# Bluetooth_LMC9830SM.net
KiCad netlist of a schematic drawn in Altium Designer
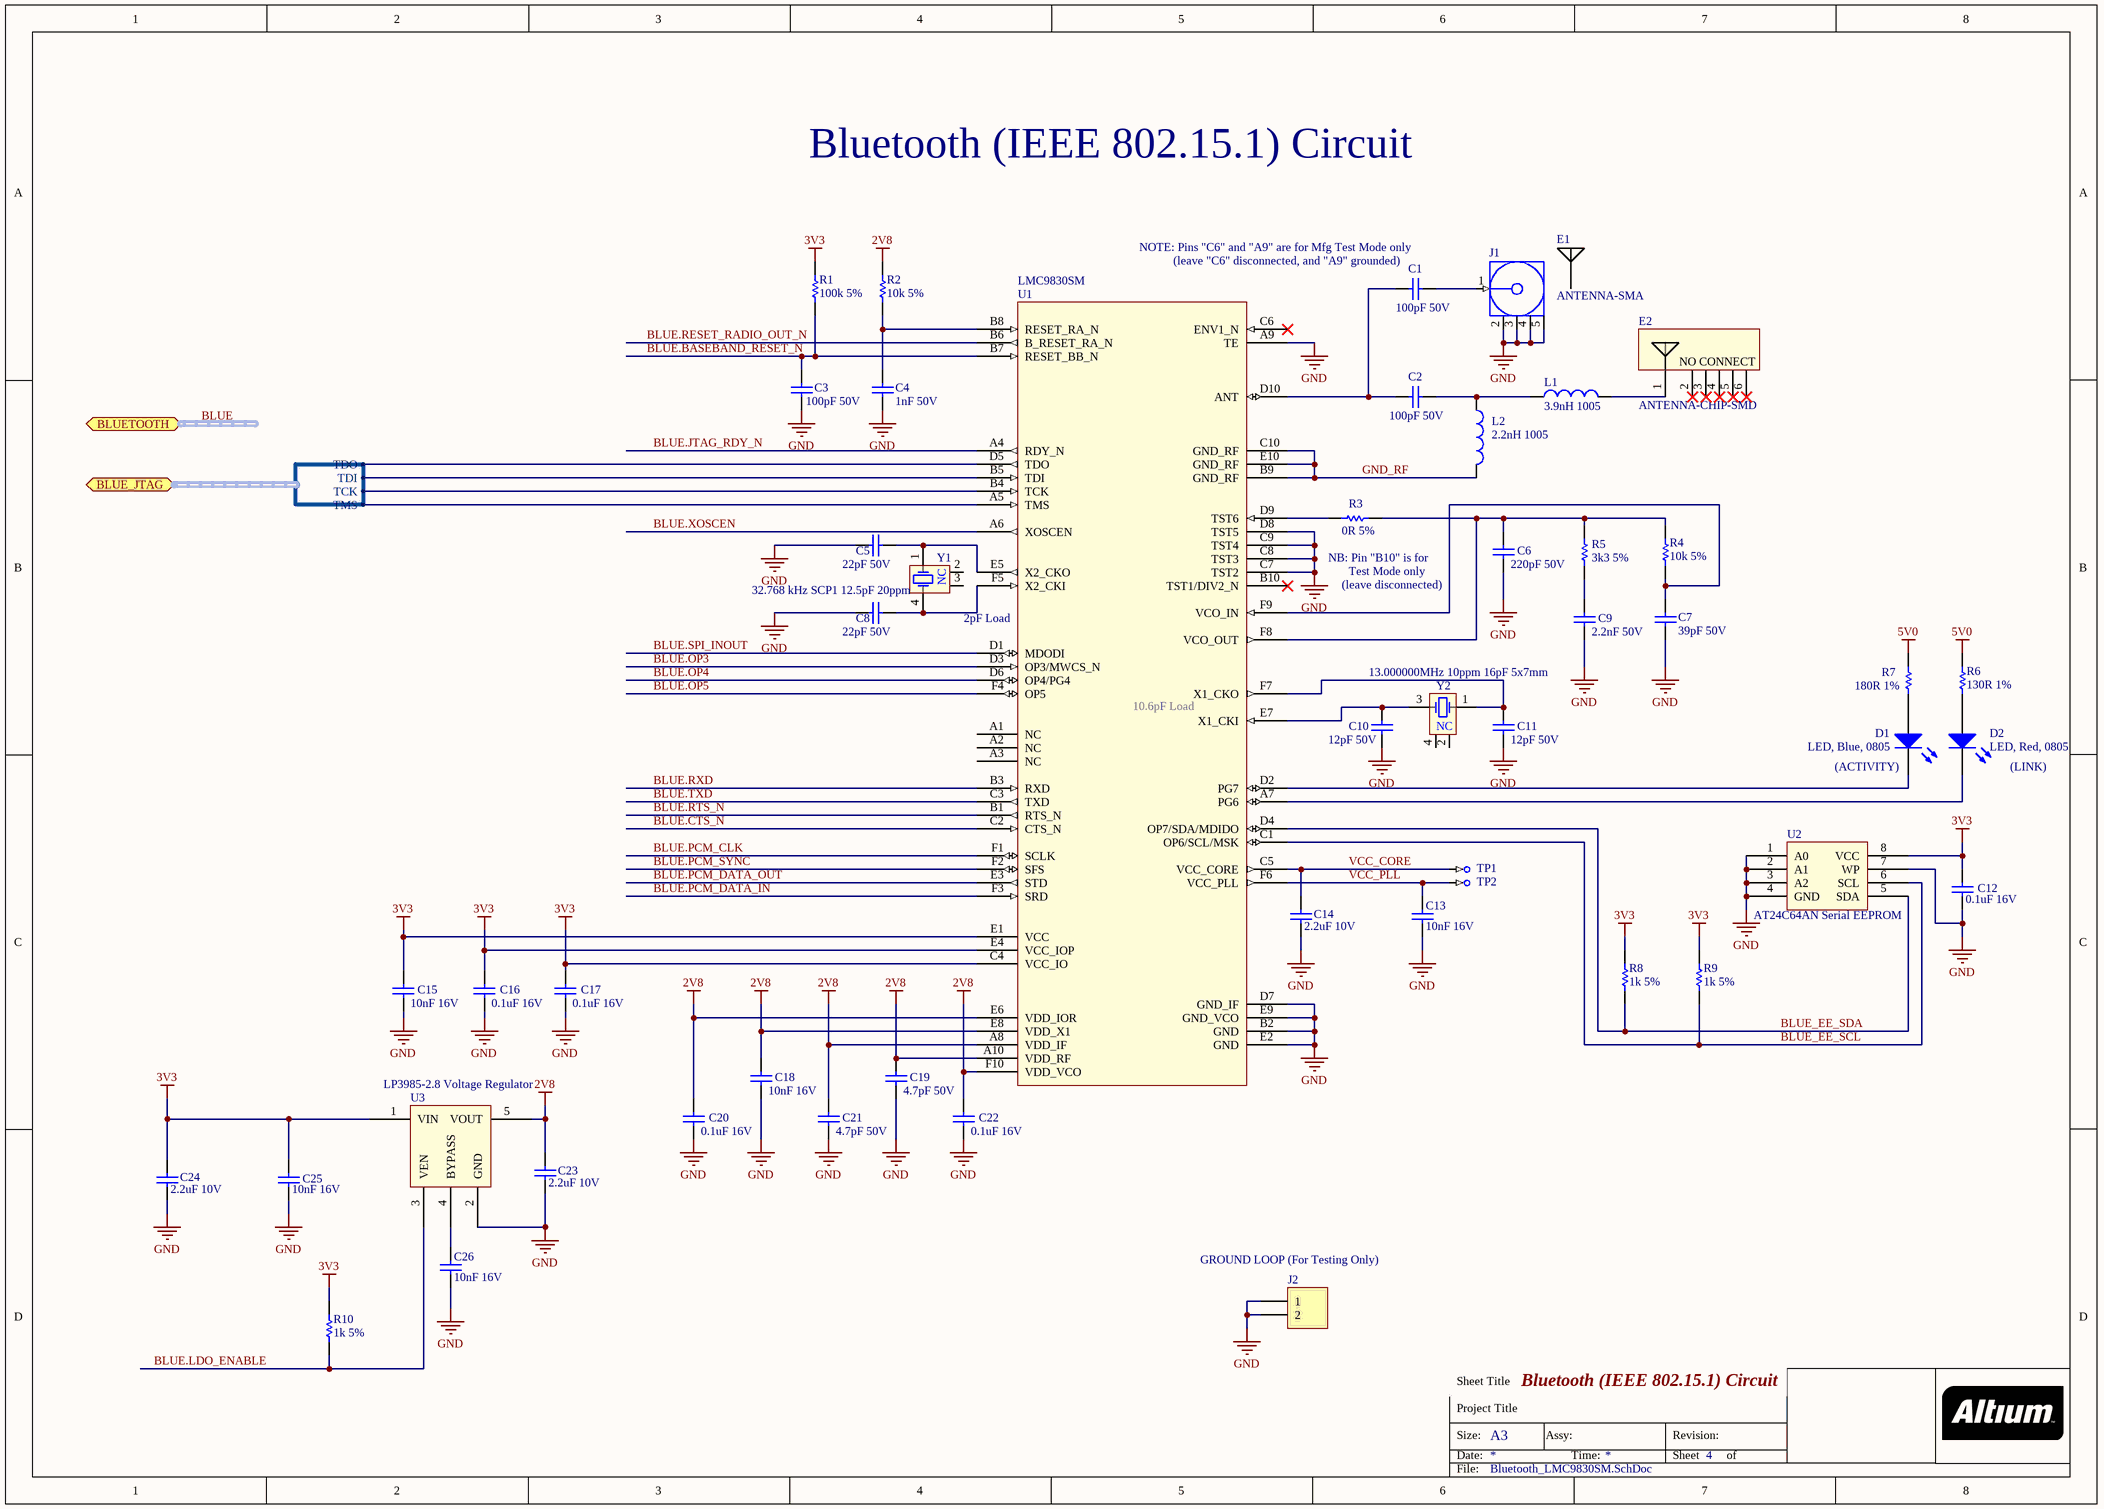
[diagram p0: Bluetooth_LMC9830SM.SchDoc]

(export (version "E")
  (design (tool "Eeschema 10.0.6"))
  (components
    (comp (ref "C1")
      (value "100pF 50V")
      (footprint "CAPC1005-STAR")
      (description "Capacitor, Ceramic, 100pF 5% 50V 0402 (1005) COG")
      (fields (field (name "TOLERANCE") "5 %"))
      (libsource (lib "AltiumDesignLibrary") (part "CAP-NP"))
    )
    (comp (ref "C2")
      (value "100pF 50V")
      (footprint "CAPC1005-STAR")
      (description "Capacitor, Ceramic, 100pF 5% 50V 0402 (1005) COG")
      (fields (field (name "TOLERANCE") "5 %"))
      (libsource (lib "AltiumDesignLibrary") (part "CAP-NP"))
    )
    (comp (ref "C3")
      (value "100pF 50V")
      (footprint "CAPC1005-STAR")
      (description "Capacitor, Ceramic, 100pF 5% 50V 0402 (1005) COG")
      (fields (field (name "TOLERANCE") "5 %"))
      (libsource (lib "AltiumDesignLibrary") (part "CAP-NP"))
    )
    (comp (ref "C4")
      (value "1nF 50V")
      (footprint "CAPC1005-STAR")
      (description "Capacitor, Ceramic, 1nF 10% 50V 0402 (1005) X7R")
      (fields (field (name "TOLERANCE") "10 %"))
      (libsource (lib "AltiumDesignLibrary") (part "CAP-NP"))
    )
    (comp (ref "C5")
      (value "22pF 50V")
      (footprint "CAPC1005-STAR")
      (description "Capacitor, Ceramic, 22pF 5% 50V 0402 (1005) COG")
      (fields (field (name "TOLERANCE") "5 %"))
      (libsource (lib "AltiumDesignLibrary") (part "CAP-NP"))
    )
    (comp (ref "C6")
      (value "220pF 50V")
      (footprint "CAPC1005-STAR")
      (description "Capacitor, Ceramic, 220pF 5% 50V 0402 (1005) COG")
      (fields (field (name "TOLERANCE") "5 %"))
      (libsource (lib "AltiumDesignLibrary") (part "CAP-NP"))
    )
    (comp (ref "C7")
      (value "39pF 50V")
      (footprint "CAPC1005-STAR")
      (description "Capacitor, Ceramic, 39pF 5% 50V 0402 (1005) COG")
      (fields (field (name "TOLERANCE") "5 %"))
      (libsource (lib "AltiumDesignLibrary") (part "CAP-NP"))
    )
    (comp (ref "C8")
      (value "22pF 50V")
      (footprint "CAPC1005-STAR")
      (description "Capacitor, Ceramic, 22pF 5% 50V 0402 (1005) COG")
      (fields (field (name "TOLERANCE") "5 %"))
      (libsource (lib "AltiumDesignLibrary") (part "CAP-NP"))
    )
    (comp (ref "C9")
      (value "2.2nF 50V")
      (footprint "CAPC1608-STAR")
      (description "Capacitor, Ceramic, 2.2nF 10% 50V 0603 (1608) X7R")
      (fields (field (name "TOLERANCE") "10 %"))
      (libsource (lib "AltiumDesignLibrary") (part "CAP-NP"))
    )
    (comp (ref "C10")
      (value "12pF 50V")
      (footprint "CAPC1005-STAR")
      (description "Capacitor, Ceramic, 12pF 2% 50V 0402 (1005) COG")
      (fields (field (name "TOLERANCE") "2 %"))
      (libsource (lib "AltiumDesignLibrary") (part "CAP-NP"))
    )
    (comp (ref "C11")
      (value "12pF 50V")
      (footprint "CAPC1005-STAR")
      (description "Capacitor, Ceramic, 12pF 2% 50V 0402 (1005) COG")
      (fields (field (name "TOLERANCE") "2 %"))
      (libsource (lib "AltiumDesignLibrary") (part "CAP-NP"))
    )
    (comp (ref "C12")
      (value "0.1uF 16V")
      (footprint "CAPC1005-STAR")
      (description "Capacitor, Ceramic, 0.1uF 10% 16V 0402 (1005) X7R")
      (fields (field (name "TOLERANCE") "10 %"))
      (libsource (lib "AltiumDesignLibrary") (part "CAP-NP"))
    )
    (comp (ref "C13")
      (value "10nF 16V")
      (footprint "CAPC1005-STAR")
      (description "Capacitor, Ceramic, 10nF 10% 16V 0402 (1005) X7R")
      (fields (field (name "TOLERANCE") "10 %"))
      (libsource (lib "AltiumDesignLibrary") (part "CAP-NP"))
    )
    (comp (ref "C14")
      (value "2.2uF 10V")
      (footprint "CAPC3216-STAR")
      (description "Capacitor, Ceramic, 2.2uF 10% 10V 1206 (3216) X7R")
      (fields (field (name "TOLERANCE") "10 %"))
      (libsource (lib "AltiumDesignLibrary") (part "CAP-NP"))
    )
    (comp (ref "C15")
      (value "10nF 16V")
      (footprint "CAPC1005-STAR")
      (description "Capacitor, Ceramic, 10nF 10% 16V 0402 (1005) X7R")
      (fields (field (name "TOLERANCE") "10 %"))
      (libsource (lib "AltiumDesignLibrary") (part "CAP-NP"))
    )
    (comp (ref "C16")
      (value "0.1uF 16V")
      (footprint "CAPC1005-STAR")
      (description "Capacitor, Ceramic, 0.1uF 10% 16V 0402 (1005) X7R")
      (fields (field (name "TOLERANCE") "10 %"))
      (libsource (lib "AltiumDesignLibrary") (part "CAP-NP"))
    )
    (comp (ref "C17")
      (value "0.1uF 16V")
      (footprint "CAPC1005-STAR")
      (description "Capacitor, Ceramic, 0.1uF 10% 16V 0402 (1005) X7R")
      (fields (field (name "TOLERANCE") "10 %"))
      (libsource (lib "AltiumDesignLibrary") (part "CAP-NP"))
    )
    (comp (ref "C18")
      (value "10nF 16V")
      (footprint "CAPC1005-STAR")
      (description "Capacitor, Ceramic, 10nF 10% 16V 0402 (1005) X7R")
      (fields (field (name "TOLERANCE") "10 %"))
      (libsource (lib "AltiumDesignLibrary") (part "CAP-NP"))
    )
    (comp (ref "C19")
      (value "4.7pF 50V")
      (footprint "CAPC1005-STAR")
      (description "Capacitor, Ceramic, 4.7pF 5% 50V 0402 (1005) COG")
      (fields (field (name "TOLERANCE") "5 %"))
      (libsource (lib "AltiumDesignLibrary") (part "CAP-NP"))
    )
    (comp (ref "C20")
      (value "0.1uF 16V")
      (footprint "CAPC1005-STAR")
      (description "Capacitor, Ceramic, 0.1uF 10% 16V 0402 (1005) X7R")
      (fields (field (name "TOLERANCE") "10 %"))
      (libsource (lib "AltiumDesignLibrary") (part "CAP-NP"))
    )
    (comp (ref "C21")
      (value "4.7pF 50V")
      (footprint "CAPC1005-STAR")
      (description "Capacitor, Ceramic, 4.7pF 5% 50V 0402 (1005) COG")
      (fields (field (name "TOLERANCE") "5 %"))
      (libsource (lib "AltiumDesignLibrary") (part "CAP-NP"))
    )
    (comp (ref "C22")
      (value "0.1uF 16V")
      (footprint "CAPC1005-STAR")
      (description "Capacitor, Ceramic, 0.1uF 10% 16V 0402 (1005) X7R")
      (fields (field (name "TOLERANCE") "10 %"))
      (libsource (lib "AltiumDesignLibrary") (part "CAP-NP"))
    )
    (comp (ref "C23")
      (value "2.2uF 10V")
      (footprint "CAPC3216-STAR")
      (description "Capacitor, Ceramic, 2.2uF 10% 10V 1206 (3216) X7R")
      (fields (field (name "TOLERANCE") "10 %"))
      (libsource (lib "AltiumDesignLibrary") (part "CAP-NP"))
    )
    (comp (ref "C24")
      (value "2.2uF 10V")
      (footprint "CAPC3216-STAR")
      (description "Capacitor, Ceramic, 2.2uF 10% 10V 1206 (3216) X7R")
      (fields (field (name "TOLERANCE") "10 %"))
      (libsource (lib "AltiumDesignLibrary") (part "CAP-NP"))
    )
    (comp (ref "C25")
      (value "10nF 16V")
      (footprint "CAPC1005-STAR")
      (description "Capacitor, Ceramic, 10nF 10% 16V 0402 (1005) X7R")
      (fields (field (name "TOLERANCE") "10 %"))
      (libsource (lib "AltiumDesignLibrary") (part "CAP-NP"))
    )
    (comp (ref "C26")
      (value "10nF 16V")
      (footprint "CAPC1005-STAR")
      (description "Capacitor, Ceramic, 10nF 10% 16V 0402 (1005) X7R")
      (fields (field (name "TOLERANCE") "10 %"))
      (libsource (lib "AltiumDesignLibrary") (part "CAP-NP"))
    )
    (comp (ref "D1")
      (value "LED, Blue, 0805")
      (footprint "LED2012-STAR")
      (description "LED, Blue 0805 (2012)")
      (libsource (lib "AltiumDesignLibrary") (part "DIO-LED-1S"))
    )
    (comp (ref "D2")
      (value "LED, Red, 0805")
      (footprint "LED2012-STAR")
      (description "LED, Red 0805 (2012) HSMH-C170")
      (libsource (lib "AltiumDesignLibrary") (part "DIO-LED-1S"))
    )
    (comp (ref "E1")
      (value "ANTENNA-SMA")
      (description "Antenna, 2.45GHz 1/4 Wave 50R SMA Antenna")
      (libsource (lib "AltiumDesignLibrary") (part "ANTENNA-0-PIN"))
    )
    (comp (ref "E2")
      (value "ANTENNA-CHIP-SMD")
      (footprint "ANTENNA-2-45GHZ-6PIN")
      (description "Antenna, 2.45GHz Chip SMD 5.5 X 7.35MM")
      (libsource (lib "AltiumDesignLibrary") (part "ANTENNA-6-PIN"))
    )
    (comp (ref "J1")
      (value "SMA 5-pin Vertical Jack 50R")
      (footprint "HDR-SMA-THD-5-PIN")
      (description "SMA RF Coaxial PCB Connector, 5-pin Through-hole, Vertical Mount Socket, 50 ohm impedance")
      (libsource (lib "AltiumDesignLibrary") (part "CON-HDR-COAXIAL-5-PIN"))
    )
    (comp (ref "J2")
      (value "1x2 HEADER MALE")
      (footprint "HDR1X2")
      (description "Header IDC, 2 x 1 Pin Vertical 2.54mm Pitch (Non-Boxed, Male)")
      (libsource (lib "AltiumDesignLibrary") (part "CON-HDR-1x2-STR"))
    )
    (comp (ref "L1")
      (value "3.9nH 1005")
      (footprint "INDC1005")
      (description "Inductor, Chip 3.9nH 300mA DCR=0.18 ohm, High Frequency 0402 (1005)")
      (libsource (lib "AltiumDesignLibrary") (part "IND"))
    )
    (comp (ref "L2")
      (value "2.2nH 1005")
      (footprint "INDC1005")
      (description "Inductor, Chip 2.2nH 300mA DCR=0.12 ohm, High Frequency 0402 (1005)")
      (libsource (lib "AltiumDesignLibrary") (part "IND"))
    )
    (comp (ref "R1")
      (value "100k 5%")
      (footprint "RESC1005-STAR")
      (description "Resistor, 100k 5% 0402 (1005)")
      (fields (field (name "TOLERANCE") "5 %"))
      (libsource (lib "AltiumDesignLibrary") (part "RES"))
    )
    (comp (ref "R2")
      (value "10k 5%")
      (footprint "RESC1005-STAR")
      (description "Resistor, 10k 5% 0402 (1005)")
      (fields (field (name "TOLERANCE") "5 %"))
      (libsource (lib "AltiumDesignLibrary") (part "RES"))
    )
    (comp (ref "R3")
      (value "0R 5%")
      (footprint "RESC1005-STAR")
      (description "Resistor, 0R 5% 0402 (1005)")
      (fields (field (name "TOLERANCE") "5 %"))
      (libsource (lib "AltiumDesignLibrary") (part "RES"))
    )
    (comp (ref "R4")
      (value "10k 5%")
      (footprint "RESC1005-STAR")
      (description "Resistor, 10k 5% 0402 (1005)")
      (fields (field (name "TOLERANCE") "5 %"))
      (libsource (lib "AltiumDesignLibrary") (part "RES"))
    )
    (comp (ref "R5")
      (value "3k3 5%")
      (footprint "RESC1005-STAR")
      (description "Resistor, 3k3 5% 0402 (1005)")
      (fields (field (name "TOLERANCE") "5 %"))
      (libsource (lib "AltiumDesignLibrary") (part "RES"))
    )
    (comp (ref "R6")
      (value "130R 1%")
      (footprint "RESC1005-STAR")
      (description "Resistor, 130R 1% 0402 (1005)")
      (fields (field (name "TOLERANCE") "1 %"))
      (libsource (lib "AltiumDesignLibrary") (part "RES"))
    )
    (comp (ref "R7")
      (value "180R 1%")
      (footprint "RESC1005-STAR")
      (description "Resistor, 180R 1% 0402 (1005)")
      (fields (field (name "TOLERANCE") "1 %"))
      (libsource (lib "AltiumDesignLibrary") (part "RES"))
    )
    (comp (ref "R8")
      (value "1k 5%")
      (footprint "RESC1005-STAR")
      (description "Resistor, 1k 5% 0402 (1005)")
      (fields (field (name "TOLERANCE") "5 %"))
      (libsource (lib "AltiumDesignLibrary") (part "RES"))
    )
    (comp (ref "R9")
      (value "1k 5%")
      (footprint "RESC1005-STAR")
      (description "Resistor, 1k 5% 0402 (1005)")
      (fields (field (name "TOLERANCE") "5 %"))
      (libsource (lib "AltiumDesignLibrary") (part "RES"))
    )
    (comp (ref "R10")
      (value "1k 5%")
      (footprint "RESC1005-STAR")
      (description "Resistor, 1k 5% 0402 (1005)")
      (fields (field (name "TOLERANCE") "5 %"))
      (libsource (lib "AltiumDesignLibrary") (part "RES"))
    )
    (comp (ref "TP1")
      (value "TestPin")
      (footprint "TestPin")
      (description "Test Point, PCB Mount with Silkscreen Box")
      (libsource (lib "AltiumDesignLibrary") (part "TestPin"))
    )
    (comp (ref "TP2")
      (value "TestPin")
      (footprint "TestPin")
      (description "Test Point, PCB Mount with Silkscreen Box")
      (libsource (lib "AltiumDesignLibrary") (part "TestPin"))
    )
    (comp (ref "U1")
      (value "LMC9830SM")
      (footprint "BGA80P9X6-60")
      (description "LMC9830SM, 2.45GHz Bluetooth Serial Port Module, BGA60")
      (libsource (lib "AltiumDesignLibrary") (part "IC-LMX9830SM"))
    )
    (comp (ref "U2")
      (value "AT24C64AN Serial EEPROM")
      (footprint "SOIC8-150-BODY")
      (description "AT24C64AN Two-Wire Serial EEPROM 2.7-5.5V SOIC-8 (JEDEC)")
      (libsource (lib "AltiumDesignLibrary") (part "IC-AT24C64"))
    )
    (comp (ref "U3")
      (value "LP3985-2.8 Voltage Regulator")
      (footprint "SOT-23-5")
      (description "LP3985IM5-2.8, 2V8 Voltage Regulator, Low-Noise Ultra Low-Dropout, 150mA, SOT-23-5")
      (libsource (lib "AltiumDesignLibrary") (part "IC-LP3985"))
    )
    (comp (ref "Y1")
      (value "32.768 kHz SCP1 12.5pF 20ppm")
      (footprint "XTAL-SCP1")
      (description "Crystal, 32.768 kHz, Surface Mount SCP1, 12.5pF, 20ppm")
      (libsource (lib "AltiumDesignLibrary") (part "CRYSTAL-4PINS-1-TO-4"))
    )
    (comp (ref "Y2")
      (value "13.000000MHz 10ppm 16pF 5x7mm")
      (footprint "XTAL-7X5")
      (description "Crystal, 13.000000MHz, 5x7mm, 10ppm 10ppm 16pF")
      (libsource (lib "AltiumDesignLibrary") (part "CRYSTAL-4PINS-1-TO-3"))
    )
  )
  (nets
    (net (code "3") (name "/BLUE.BASEBAND_RESET_N") (class "Default")
      (node (ref "C3") (pin "2") (pinfunction "2_2") (pintype "passive"))
      (node (ref "R1") (pin "2") (pinfunction "2_2") (pintype "passive"))
      (node (ref "U1") (pin "B7") (pinfunction "RESET_BB_N_B7") (pintype "input"))
    )
    (net (code "4") (name "/BLUE.CTS_N") (class "Default")
      (node (ref "U1") (pin "C2") (pinfunction "CTS_N_C2") (pintype "input"))
    )
    (net (code "5") (name "/BLUE.JTAG_RDY_N") (class "Default")
      (node (ref "U1") (pin "A4") (pinfunction "RDY_N_A4") (pintype "output"))
    )
    (net (code "6") (name "/BLUE.LDO_ENABLE") (class "Default")
      (node (ref "R10") (pin "2") (pinfunction "2_2") (pintype "passive"))
      (node (ref "U3") (pin "3") (pinfunction "VEN_3") (pintype "passive"))
    )
    (net (code "7") (name "/BLUE.OP3") (class "Default")
      (node (ref "U1") (pin "D3") (pinfunction "OP3/MWCS_N_D3") (pintype "input"))
    )
    (net (code "8") (name "/BLUE.OP4") (class "Default")
      (node (ref "U1") (pin "D6") (pinfunction "OP4/PG4_D6") (pintype "bidirectional"))
    )
    (net (code "9") (name "/BLUE.OP5") (class "Default")
      (node (ref "U1") (pin "F4") (pinfunction "OP5_F4") (pintype "bidirectional"))
    )
    (net (code "10") (name "/BLUE.PCM_CLK") (class "Default")
      (node (ref "U1") (pin "F1") (pinfunction "SCLK_F1") (pintype "bidirectional"))
    )
    (net (code "11") (name "/BLUE.PCM_DATA_IN") (class "Default")
      (node (ref "U1") (pin "F3") (pinfunction "SRD_F3") (pintype "input"))
    )
    (net (code "12") (name "/BLUE.PCM_DATA_OUT") (class "Default")
      (node (ref "U1") (pin "E3") (pinfunction "STD_E3") (pintype "output"))
    )
    (net (code "13") (name "/BLUE.PCM_SYNC") (class "Default")
      (node (ref "U1") (pin "F2") (pinfunction "SFS_F2") (pintype "bidirectional"))
    )
    (net (code "14") (name "/BLUE.RESET_RADIO_OUT_N") (class "Default")
      (node (ref "U1") (pin "B6") (pinfunction "B_RESET_RA_N_B6") (pintype "output"))
    )
    (net (code "15") (name "/BLUE.RTS_N") (class "Default")
      (node (ref "U1") (pin "B1") (pinfunction "RTS_N_B1") (pintype "output"))
    )
    (net (code "16") (name "/BLUE.RXD") (class "Default")
      (node (ref "U1") (pin "B3") (pinfunction "RXD_B3") (pintype "input"))
    )
    (net (code "17") (name "/BLUE.SPI_INOUT") (class "Default")
      (node (ref "U1") (pin "D1") (pinfunction "MDODI_D1") (pintype "bidirectional"))
    )
    (net (code "18") (name "/BLUE.TXD") (class "Default")
      (node (ref "U1") (pin "C3") (pinfunction "TXD_C3") (pintype "output"))
    )
    (net (code "19") (name "/BLUE.XOSCEN") (class "Default")
      (node (ref "U1") (pin "A6") (pinfunction "XOSCEN_A6") (pintype "output"))
    )
    (net (code "20") (name "/BLUE_EE_SCL") (class "Default")
      (node (ref "R9") (pin "2") (pinfunction "2_2") (pintype "passive"))
      (node (ref "U1") (pin "C1") (pinfunction "OP6/SCL/MSK_C1") (pintype "bidirectional"))
      (node (ref "U2") (pin "6") (pinfunction "SCL_6") (pintype "passive"))
    )
    (net (code "21") (name "/BLUE_EE_SDA") (class "Default")
      (node (ref "R8") (pin "2") (pinfunction "2_2") (pintype "passive"))
      (node (ref "U1") (pin "D4") (pinfunction "OP7/SDA/MDIDO_D4") (pintype "bidirectional"))
      (node (ref "U2") (pin "5") (pinfunction "SDA_5") (pintype "passive"))
    )
    (net (code "22") (name "/GND_RF") (class "Default")
      (node (ref "L2") (pin "2") (pinfunction "2_2") (pintype "passive"))
      (node (ref "U1") (pin "B9") (pinfunction "GND_RF_B9") (pintype "power_in"))
      (node (ref "U1") (pin "C10") (pinfunction "GND_RF_C10") (pintype "power_in"))
      (node (ref "U1") (pin "E10") (pinfunction "GND_RF_E10") (pintype "power_in"))
    )
    (net (code "23") (name "/TCK") (class "Default")
      (node (ref "U1") (pin "B4") (pinfunction "TCK_B4") (pintype "input"))
    )
    (net (code "24") (name "/TDI") (class "Default")
      (node (ref "U1") (pin "B5") (pinfunction "TDI_B5") (pintype "input"))
    )
    (net (code "25") (name "/TDO") (class "Default")
      (node (ref "U1") (pin "D5") (pinfunction "TDO_D5") (pintype "output"))
    )
    (net (code "26") (name "/TMS") (class "Default")
      (node (ref "U1") (pin "A5") (pinfunction "TMS_A5") (pintype "input"))
    )
    (net (code "27") (name "/VCC_CORE") (class "Default")
      (node (ref "C14") (pin "1") (pinfunction "1_1") (pintype "passive"))
      (node (ref "TP1") (pin "1") (pinfunction "1_1") (pintype "input"))
      (node (ref "U1") (pin "C5") (pinfunction "VCC_CORE_C5") (pintype "output"))
    )
    (net (code "28") (name "/VCC_PLL") (class "Default")
      (node (ref "C13") (pin "1") (pinfunction "1_1") (pintype "passive"))
      (node (ref "TP2") (pin "1") (pinfunction "1_1") (pintype "input"))
      (node (ref "U1") (pin "F6") (pinfunction "VCC_PLL_F6") (pintype "output"))
    )
    (net (code "31") (name "2V8") (class "Default")
      (node (ref "C18") (pin "1") (pinfunction "1_1") (pintype "passive"))
      (node (ref "C19") (pin "1") (pinfunction "1_1") (pintype "passive"))
      (node (ref "C20") (pin "1") (pinfunction "1_1") (pintype "passive"))
      (node (ref "C21") (pin "1") (pinfunction "1_1") (pintype "passive"))
      (node (ref "C22") (pin "1") (pinfunction "1_1") (pintype "passive"))
      (node (ref "C23") (pin "1") (pinfunction "1_1") (pintype "passive"))
      (node (ref "R2") (pin "1") (pinfunction "1_1") (pintype "passive"))
      (node (ref "U1") (pin "A10") (pinfunction "VDD_RF_A10") (pintype "passive"))
      (node (ref "U1") (pin "A8") (pinfunction "VDD_IF_A8") (pintype "passive"))
      (node (ref "U1") (pin "E6") (pinfunction "VDD_IOR_E6") (pintype "passive"))
      (node (ref "U1") (pin "E8") (pinfunction "VDD_X1_E8") (pintype "passive"))
      (node (ref "U1") (pin "F10") (pinfunction "VDD_VCO_F10") (pintype "passive"))
      (node (ref "U3") (pin "5") (pinfunction "VOUT_5") (pintype "passive"))
    )
    (net (code "32") (name "3V3") (class "Default")
      (node (ref "C12") (pin "1") (pinfunction "1_1") (pintype "passive"))
      (node (ref "C15") (pin "1") (pinfunction "1_1") (pintype "passive"))
      (node (ref "C16") (pin "1") (pinfunction "1_1") (pintype "passive"))
      (node (ref "C17") (pin "1") (pinfunction "1_1") (pintype "passive"))
      (node (ref "C24") (pin "1") (pinfunction "1_1") (pintype "passive"))
      (node (ref "C25") (pin "1") (pinfunction "1_1") (pintype "passive"))
      (node (ref "R1") (pin "1") (pinfunction "1_1") (pintype "passive"))
      (node (ref "R10") (pin "1") (pinfunction "1_1") (pintype "passive"))
      (node (ref "R8") (pin "1") (pinfunction "1_1") (pintype "passive"))
      (node (ref "R9") (pin "1") (pinfunction "1_1") (pintype "passive"))
      (node (ref "U1") (pin "C4") (pinfunction "VCC_IO_C4") (pintype "power_in"))
      (node (ref "U1") (pin "E1") (pinfunction "VCC_E1") (pintype "power_in"))
      (node (ref "U1") (pin "E4") (pinfunction "VCC_IOP_E4") (pintype "power_in"))
      (node (ref "U2") (pin "8") (pinfunction "VCC_8") (pintype "passive"))
      (node (ref "U3") (pin "1") (pinfunction "VIN_1") (pintype "passive"))
    )
    (net (code "33") (name "5V0") (class "Default")
      (node (ref "R6") (pin "1") (pinfunction "1_1") (pintype "passive"))
      (node (ref "R7") (pin "1") (pinfunction "1_1") (pintype "passive"))
    )
    (net (code "34") (name "GND") (class "Default")
      (node (ref "C10") (pin "2") (pinfunction "2_2") (pintype "passive"))
      (node (ref "C11") (pin "2") (pinfunction "2_2") (pintype "passive"))
      (node (ref "C12") (pin "2") (pinfunction "2_2") (pintype "passive"))
      (node (ref "C13") (pin "2") (pinfunction "2_2") (pintype "passive"))
      (node (ref "C14") (pin "2") (pinfunction "2_2") (pintype "passive"))
      (node (ref "C15") (pin "2") (pinfunction "2_2") (pintype "passive"))
      (node (ref "C16") (pin "2") (pinfunction "2_2") (pintype "passive"))
      (node (ref "C17") (pin "2") (pinfunction "2_2") (pintype "passive"))
      (node (ref "C18") (pin "2") (pinfunction "2_2") (pintype "passive"))
      (node (ref "C19") (pin "2") (pinfunction "2_2") (pintype "passive"))
      (node (ref "C20") (pin "2") (pinfunction "2_2") (pintype "passive"))
      (node (ref "C21") (pin "2") (pinfunction "2_2") (pintype "passive"))
      (node (ref "C22") (pin "2") (pinfunction "2_2") (pintype "passive"))
      (node (ref "C23") (pin "2") (pinfunction "2_2") (pintype "passive"))
      (node (ref "C24") (pin "2") (pinfunction "2_2") (pintype "passive"))
      (node (ref "C25") (pin "2") (pinfunction "2_2") (pintype "passive"))
      (node (ref "C26") (pin "2") (pinfunction "2_2") (pintype "passive"))
      (node (ref "C3") (pin "1") (pinfunction "1_1") (pintype "passive"))
      (node (ref "C4") (pin "2") (pinfunction "2_2") (pintype "passive"))
      (node (ref "C5") (pin "1") (pinfunction "1_1") (pintype "passive"))
      (node (ref "C6") (pin "2") (pinfunction "2_2") (pintype "passive"))
      (node (ref "C7") (pin "2") (pinfunction "2_2") (pintype "passive"))
      (node (ref "C8") (pin "1") (pinfunction "1_1") (pintype "passive"))
      (node (ref "C9") (pin "2") (pinfunction "2_2") (pintype "passive"))
      (node (ref "J1") (pin "2") (pinfunction "GND_2") (pintype "passive"))
      (node (ref "J1") (pin "3") (pinfunction "GND_3") (pintype "passive"))
      (node (ref "J1") (pin "4") (pinfunction "GND_4") (pintype "passive"))
      (node (ref "J1") (pin "5") (pinfunction "GND_5") (pintype "passive"))
      (node (ref "J2") (pin "1") (pinfunction "1_1") (pintype "passive"))
      (node (ref "J2") (pin "2") (pinfunction "2_2") (pintype "passive"))
      (node (ref "U1") (pin "A9") (pinfunction "TE_A9") (pintype "passive"))
      (node (ref "U1") (pin "B2") (pinfunction "GND_B2") (pintype "power_in"))
      (node (ref "U1") (pin "C7") (pinfunction "TST2_C7") (pintype "passive"))
      (node (ref "U1") (pin "C8") (pinfunction "TST3_C8") (pintype "passive"))
      (node (ref "U1") (pin "C9") (pinfunction "TST4_C9") (pintype "passive"))
      (node (ref "U1") (pin "D7") (pinfunction "GND_IF_D7") (pintype "power_in"))
      (node (ref "U1") (pin "D8") (pinfunction "TST5_D8") (pintype "passive"))
      (node (ref "U1") (pin "E2") (pinfunction "GND_E2") (pintype "power_in"))
      (node (ref "U1") (pin "E9") (pinfunction "GND_VCO_E9") (pintype "power_in"))
      (node (ref "U2") (pin "1") (pinfunction "A0_1") (pintype "passive"))
      (node (ref "U2") (pin "2") (pinfunction "A1_2") (pintype "passive"))
      (node (ref "U2") (pin "3") (pinfunction "A2_3") (pintype "passive"))
      (node (ref "U2") (pin "4") (pinfunction "GND_4") (pintype "passive"))
      (node (ref "U2") (pin "7") (pinfunction "WP_7") (pintype "passive"))
      (node (ref "U3") (pin "2") (pinfunction "GND_2") (pintype "passive"))
    )
    (net (code "35") (name "Net-(C2-Pad2)") (class "Default")
      (node (ref "C2") (pin "2") (pinfunction "2_2") (pintype "passive"))
      (node (ref "L1") (pin "1") (pinfunction "1_1") (pintype "passive"))
      (node (ref "L2") (pin "1") (pinfunction "1_1") (pintype "passive"))
    )
    (net (code "36") (name "Net-(C9-Pad1)") (class "Default")
      (node (ref "C9") (pin "1") (pinfunction "1_1") (pintype "passive"))
      (node (ref "R5") (pin "2") (pinfunction "2_2") (pintype "passive"))
    )
    (net (code "37") (name "Net-(D1-A)") (class "Default")
      (node (ref "D1") (pin "1") (pinfunction "A_1") (pintype "passive"))
      (node (ref "R7") (pin "2") (pinfunction "2_2") (pintype "passive"))
    )
    (net (code "38") (name "Net-(D1-K)") (class "Default")
      (node (ref "D1") (pin "2") (pinfunction "K_2") (pintype "passive"))
      (node (ref "U1") (pin "D2") (pinfunction "PG7_D2") (pintype "bidirectional"))
    )
    (net (code "39") (name "Net-(D2-A)") (class "Default")
      (node (ref "D2") (pin "1") (pinfunction "A_1") (pintype "passive"))
      (node (ref "R6") (pin "2") (pinfunction "2_2") (pintype "passive"))
    )
    (net (code "40") (name "Net-(D2-K)") (class "Default")
      (node (ref "D2") (pin "2") (pinfunction "K_2") (pintype "passive"))
      (node (ref "U1") (pin "A7") (pinfunction "PG6_A7") (pintype "bidirectional"))
    )
    (net (code "41") (name "Net-(E2-Pad1)") (class "Default")
      (node (ref "E2") (pin "1") (pinfunction "1_1") (pintype "passive"))
      (node (ref "L1") (pin "2") (pinfunction "2_2") (pintype "passive"))
    )
    (net (code "42") (name "Net-(J1-Signal)") (class "Default")
      (node (ref "C1") (pin "2") (pinfunction "2_2") (pintype "passive"))
      (node (ref "J1") (pin "1") (pinfunction "Signal_1") (pintype "input"))
    )
    (net (code "43") (name "Net-(U1-ANT)") (class "Default")
      (node (ref "C1") (pin "1") (pinfunction "1_1") (pintype "passive"))
      (node (ref "C2") (pin "1") (pinfunction "1_1") (pintype "passive"))
      (node (ref "U1") (pin "D10") (pinfunction "ANT_D10") (pintype "bidirectional"))
    )
    (net (code "44") (name "Net-(U1-RESET_RA_N)") (class "Default")
      (node (ref "C4") (pin "1") (pinfunction "1_1") (pintype "passive"))
      (node (ref "R2") (pin "2") (pinfunction "2_2") (pintype "passive"))
      (node (ref "U1") (pin "B8") (pinfunction "RESET_RA_N_B8") (pintype "input"))
    )
    (net (code "45") (name "Net-(U1-TST6)") (class "Default")
      (node (ref "R3") (pin "1") (pinfunction "1_1") (pintype "passive"))
      (node (ref "U1") (pin "D9") (pinfunction "TST6_D9") (pintype "input"))
    )
    (net (code "46") (name "Net-(U1-VCO_IN)") (class "Default")
      (node (ref "C7") (pin "1") (pinfunction "1_1") (pintype "passive"))
      (node (ref "R4") (pin "2") (pinfunction "2_2") (pintype "passive"))
      (node (ref "U1") (pin "F9") (pinfunction "VCO_IN_F9") (pintype "input"))
    )
    (net (code "47") (name "Net-(U1-VCO_OUT)") (class "Default")
      (node (ref "C6") (pin "1") (pinfunction "1_1") (pintype "passive"))
      (node (ref "R3") (pin "2") (pinfunction "2_2") (pintype "passive"))
      (node (ref "R4") (pin "1") (pinfunction "1_1") (pintype "passive"))
      (node (ref "R5") (pin "1") (pinfunction "1_1") (pintype "passive"))
      (node (ref "U1") (pin "F8") (pinfunction "VCO_OUT_F8") (pintype "output"))
    )
    (net (code "48") (name "Net-(U1-X1_CKI)") (class "Default")
      (node (ref "C10") (pin "1") (pinfunction "1_1") (pintype "passive"))
      (node (ref "U1") (pin "E7") (pinfunction "X1_CKI_E7") (pintype "input"))
      (node (ref "Y2") (pin "3") (pinfunction "X2_3") (pintype "passive"))
    )
    (net (code "49") (name "Net-(U1-X1_CKO)") (class "Default")
      (node (ref "C11") (pin "1") (pinfunction "1_1") (pintype "passive"))
      (node (ref "U1") (pin "F7") (pinfunction "X1_CKO_F7") (pintype "output"))
      (node (ref "Y2") (pin "1") (pinfunction "X1_1") (pintype "passive"))
    )
    (net (code "50") (name "Net-(U1-X2_CKI)") (class "Default")
      (node (ref "C8") (pin "2") (pinfunction "2_2") (pintype "passive"))
      (node (ref "U1") (pin "F5") (pinfunction "X2_CKI_F5") (pintype "input"))
      (node (ref "Y1") (pin "4") (pinfunction "X2_4") (pintype "passive"))
    )
    (net (code "51") (name "Net-(U1-X2_CKO)") (class "Default")
      (node (ref "C5") (pin "2") (pinfunction "2_2") (pintype "passive"))
      (node (ref "U1") (pin "E5") (pinfunction "X2_CKO_E5") (pintype "output"))
      (node (ref "Y1") (pin "1") (pinfunction "X1_1") (pintype "passive"))
    )
    (net (code "52") (name "Net-(U3-BYPASS)") (class "Default")
      (node (ref "C26") (pin "1") (pinfunction "1_1") (pintype "passive"))
      (node (ref "U3") (pin "4") (pinfunction "BYPASS_4") (pintype "passive"))
    )
    (net (code "53") (name "unconnected-(E2-Pad2)") (class "Default")
      (node (ref "E2") (pin "2") (pinfunction "2_2") (pintype "passive+no_connect"))
    )
    (net (code "54") (name "unconnected-(E2-Pad3)") (class "Default")
      (node (ref "E2") (pin "3") (pinfunction "3_3") (pintype "passive+no_connect"))
    )
    (net (code "55") (name "unconnected-(E2-Pad4)") (class "Default")
      (node (ref "E2") (pin "4") (pinfunction "4_4") (pintype "passive+no_connect"))
    )
    (net (code "56") (name "unconnected-(E2-Pad5)") (class "Default")
      (node (ref "E2") (pin "5") (pinfunction "5_5") (pintype "passive+no_connect"))
    )
    (net (code "57") (name "unconnected-(E2-Pad6)") (class "Default")
      (node (ref "E2") (pin "6") (pinfunction "6_6") (pintype "passive+no_connect"))
    )
    (net (code "58") (name "unconnected-(U1-ENV1_N-PadC6)") (class "Default")
      (node (ref "U1") (pin "C6") (pinfunction "ENV1_N_C6") (pintype "input+no_connect"))
    )
    (net (code "59") (name "unconnected-(U1-NC-PadA1)") (class "Default")
      (node (ref "U1") (pin "A1") (pinfunction "NC_A1") (pintype "passive"))
    )
    (net (code "60") (name "unconnected-(U1-NC-PadA2)") (class "Default")
      (node (ref "U1") (pin "A2") (pinfunction "NC_A2") (pintype "passive"))
    )
    (net (code "61") (name "unconnected-(U1-NC-PadA3)") (class "Default")
      (node (ref "U1") (pin "A3") (pinfunction "NC_A3") (pintype "passive"))
    )
    (net (code "62") (name "unconnected-(U1-TST1{slash}DIV2_N-PadB10)") (class "Default")
      (node (ref "U1") (pin "B10") (pinfunction "TST1/DIV2_N_B10") (pintype "passive+no_connect"))
    )
    (net (code "63") (name "unconnected-(Y1-NC-Pad2)") (class "Default")
      (node (ref "Y1") (pin "2") (pinfunction "NC_2") (pintype "passive"))
    )
    (net (code "64") (name "unconnected-(Y1-NC-Pad3)") (class "Default")
      (node (ref "Y1") (pin "3") (pinfunction "NC_3") (pintype "passive"))
    )
    (net (code "65") (name "unconnected-(Y2-NC-Pad2)") (class "Default")
      (node (ref "Y2") (pin "2") (pinfunction "NC_2") (pintype "passive"))
    )
    (net (code "66") (name "unconnected-(Y2-NC-Pad4)") (class "Default")
      (node (ref "Y2") (pin "4") (pinfunction "NC_4") (pintype "passive"))
    )
  )
)
